# WiFi_RoboCut_v1.net
KiCad netlist of a schematic drawn in EAGLE
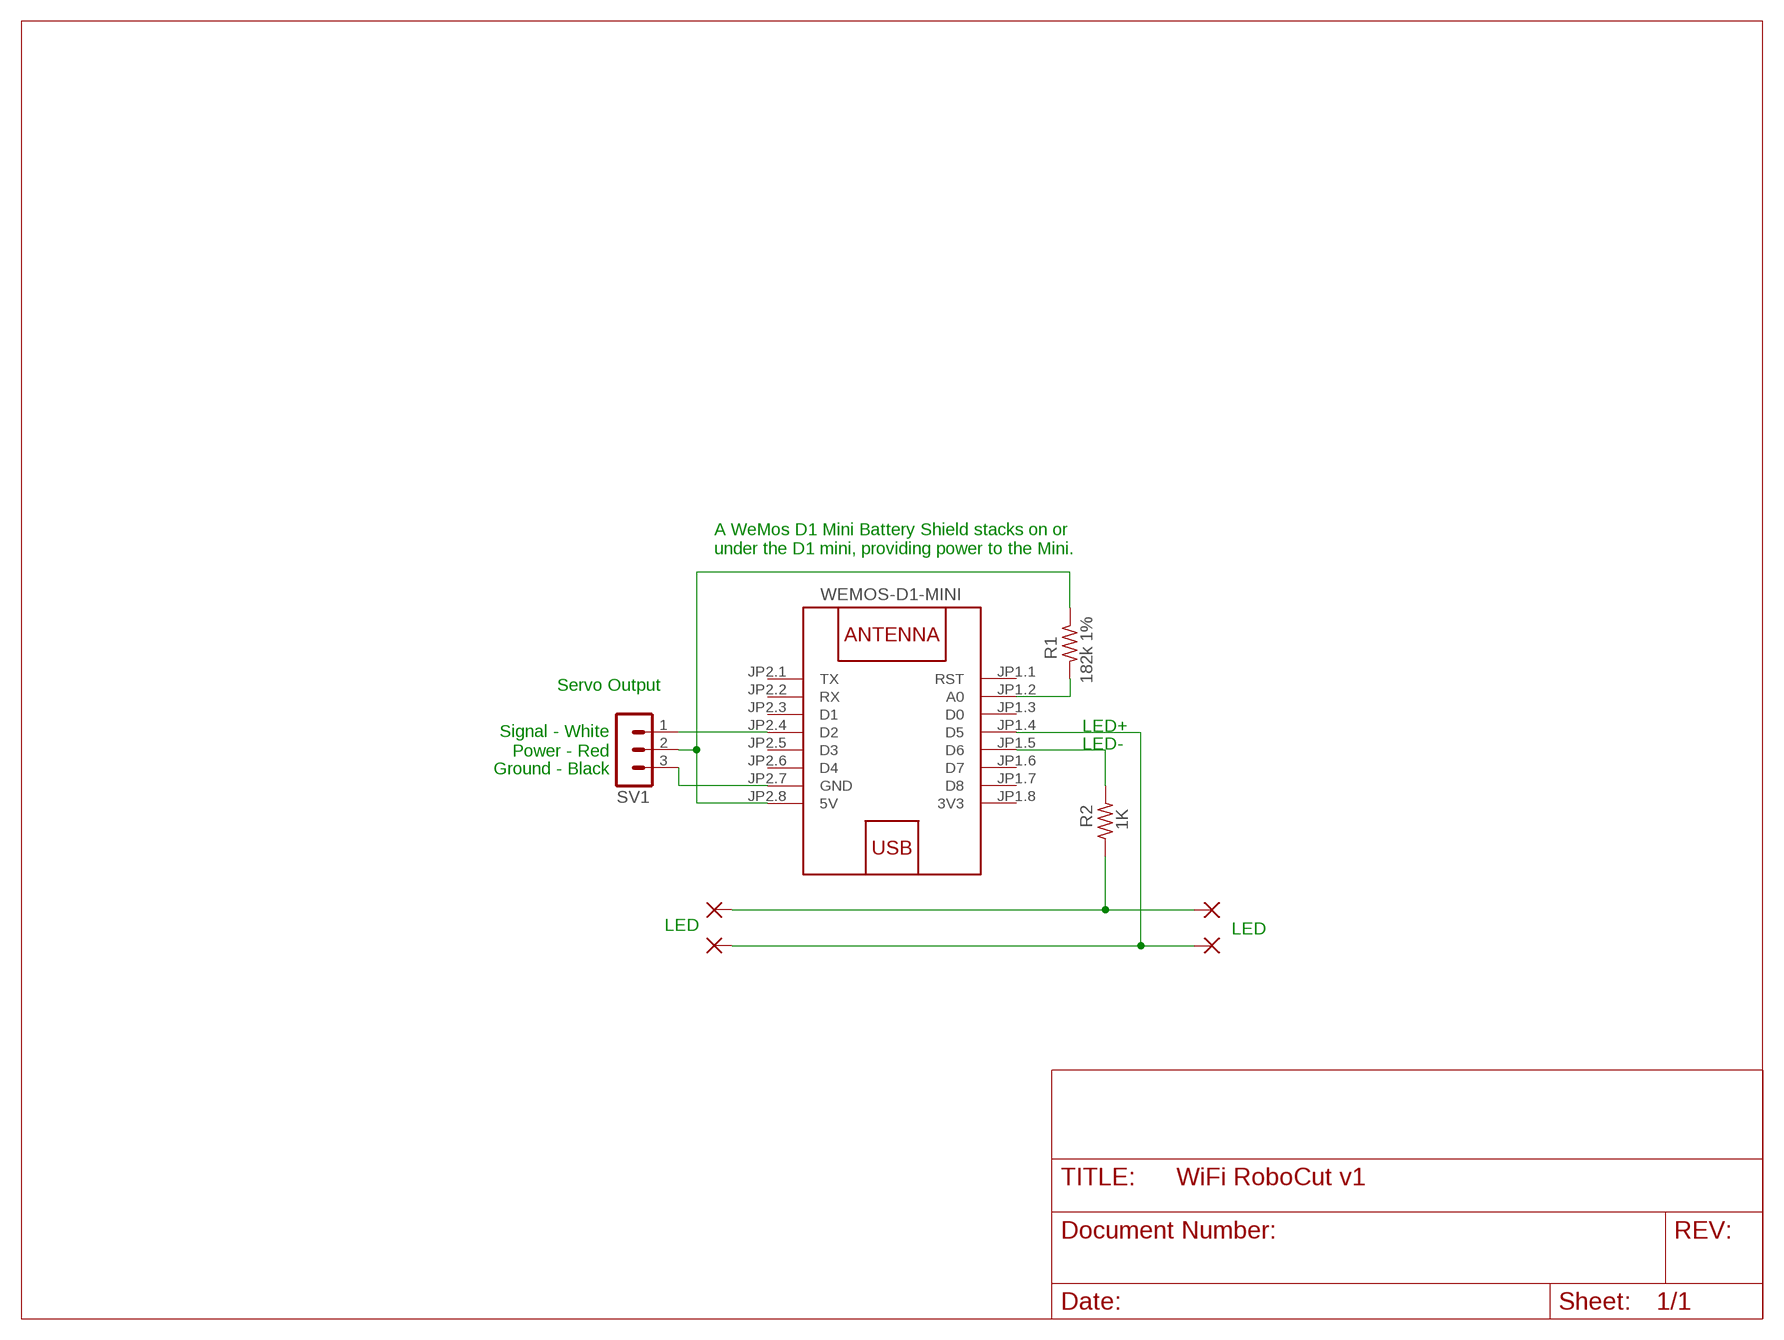
[diagram p0: schematic, sheet 1]

(export (version "E")
  (design (tool "Eeschema 10.0.6"))
  (components
    (comp (ref "PAD1")
      (value "2,15/1,0")
      (footprint "eagle-import:2,15_1,0")
      (libsource (lib "eagle-import") (part "2,15/1,0"))
    )
    (comp (ref "PAD2")
      (value "2,15/1,0")
      (footprint "eagle-import:2,15_1,0")
      (libsource (lib "eagle-import") (part "2,15/1,0"))
    )
    (comp (ref "PAD3")
      (value "2,15/1,0")
      (footprint "eagle-import:2,15_1,0")
      (libsource (lib "eagle-import") (part "2,15/1,0"))
    )
    (comp (ref "PAD4")
      (value "2,15/1,0")
      (footprint "eagle-import:2,15_1,0")
      (libsource (lib "eagle-import") (part "2,15/1,0"))
    )
    (comp (ref "R1")
      (value "182k 1%")
      (footprint "eagle-import:R1206")
      (libsource (lib "eagle-import") (part "R-US_R1206"))
    )
    (comp (ref "R2")
      (value "1K")
      (footprint "eagle-import:R1206")
      (libsource (lib "eagle-import") (part "R-US_R1206"))
    )
    (comp (ref "SV1")
      (value "MA03-1")
      (footprint "eagle-import:MA03-1")
      (libsource (lib "eagle-import") (part "MA03-1"))
    )
    (comp (ref "U$1")
      (value "WEMOS-D1-MINI")
      (footprint "eagle-import:WEMOS-D1-MINI")
      (libsource (lib "eagle-import") (part "WEMOS-D1-MINI"))
    )
  )
  (nets
    (net (code "1") (name "/3V3") (class "Default")
      (node (ref "U$1") (pin "JP1.8") (pinfunction "3V3_JP1.8") (pintype "power_in"))
    )
    (net (code "2") (name "Net-(PAD1-P)") (class "Default")
      (node (ref "PAD1") (pin "1") (pinfunction "P_1") (pintype "passive"))
      (node (ref "PAD3") (pin "1") (pinfunction "P_1") (pintype "passive"))
      (node (ref "R2") (pin "1") (pinfunction "1_1") (pintype "passive"))
    )
    (net (code "3") (name "Net-(PAD2-P)") (class "Default")
      (node (ref "PAD2") (pin "1") (pinfunction "P_1") (pintype "passive"))
      (node (ref "PAD4") (pin "1") (pinfunction "P_1") (pintype "passive"))
      (node (ref "U$1") (pin "JP1.4") (pinfunction "D5_JP1.4") (pintype "bidirectional"))
    )
    (net (code "4") (name "Net-(U$1-5V)") (class "Default")
      (node (ref "R1") (pin "1") (pinfunction "1_1") (pintype "passive"))
      (node (ref "SV1") (pin "2") (pinfunction "2_2") (pintype "passive"))
      (node (ref "U$1") (pin "JP2.8") (pinfunction "5V_JP2.8") (pintype "power_in"))
    )
    (net (code "5") (name "Net-(U$1-A0)") (class "Default")
      (node (ref "R1") (pin "2") (pinfunction "2_2") (pintype "passive"))
      (node (ref "U$1") (pin "JP1.2") (pinfunction "A0_JP1.2") (pintype "bidirectional"))
    )
    (net (code "6") (name "Net-(U$1-D2)") (class "Default")
      (node (ref "SV1") (pin "1") (pinfunction "1_1") (pintype "passive"))
      (node (ref "U$1") (pin "JP2.4") (pinfunction "D2_JP2.4") (pintype "bidirectional"))
    )
    (net (code "7") (name "Net-(U$1-D6)") (class "Default")
      (node (ref "R2") (pin "2") (pinfunction "2_2") (pintype "passive"))
      (node (ref "U$1") (pin "JP1.5") (pinfunction "D6_JP1.5") (pintype "bidirectional"))
    )
    (net (code "8") (name "Net-(U$1-GND)") (class "Default")
      (node (ref "SV1") (pin "3") (pinfunction "3_3") (pintype "passive"))
      (node (ref "U$1") (pin "JP2.7") (pinfunction "GND_JP2.7") (pintype "power_in"))
    )
    (net (code "9") (name "unconnected-(U$1-D0-PadJP1.3)") (class "Default")
      (node (ref "U$1") (pin "JP1.3") (pinfunction "D0_JP1.3") (pintype "bidirectional"))
    )
    (net (code "10") (name "unconnected-(U$1-D1-PadJP2.3)") (class "Default")
      (node (ref "U$1") (pin "JP2.3") (pinfunction "D1_JP2.3") (pintype "bidirectional"))
    )
    (net (code "11") (name "unconnected-(U$1-D3-PadJP2.5)") (class "Default")
      (node (ref "U$1") (pin "JP2.5") (pinfunction "D3_JP2.5") (pintype "bidirectional"))
    )
    (net (code "12") (name "unconnected-(U$1-D4-PadJP2.6)") (class "Default")
      (node (ref "U$1") (pin "JP2.6") (pinfunction "D4_JP2.6") (pintype "bidirectional"))
    )
    (net (code "13") (name "unconnected-(U$1-D7-PadJP1.6)") (class "Default")
      (node (ref "U$1") (pin "JP1.6") (pinfunction "D7_JP1.6") (pintype "bidirectional"))
    )
    (net (code "14") (name "unconnected-(U$1-D8-PadJP1.7)") (class "Default")
      (node (ref "U$1") (pin "JP1.7") (pinfunction "D8_JP1.7") (pintype "bidirectional"))
    )
    (net (code "15") (name "unconnected-(U$1-RST-PadJP1.1)") (class "Default")
      (node (ref "U$1") (pin "JP1.1") (pinfunction "RST_JP1.1") (pintype "bidirectional"))
    )
    (net (code "16") (name "unconnected-(U$1-RX-PadJP2.2)") (class "Default")
      (node (ref "U$1") (pin "JP2.2") (pinfunction "RX_JP2.2") (pintype "bidirectional"))
    )
    (net (code "17") (name "unconnected-(U$1-TX-PadJP2.1)") (class "Default")
      (node (ref "U$1") (pin "JP2.1") (pinfunction "TX_JP2.1") (pintype "bidirectional"))
    )
  )
)
